# Sheet1.net
KiCad netlist of a schematic drawn in Altium Designer
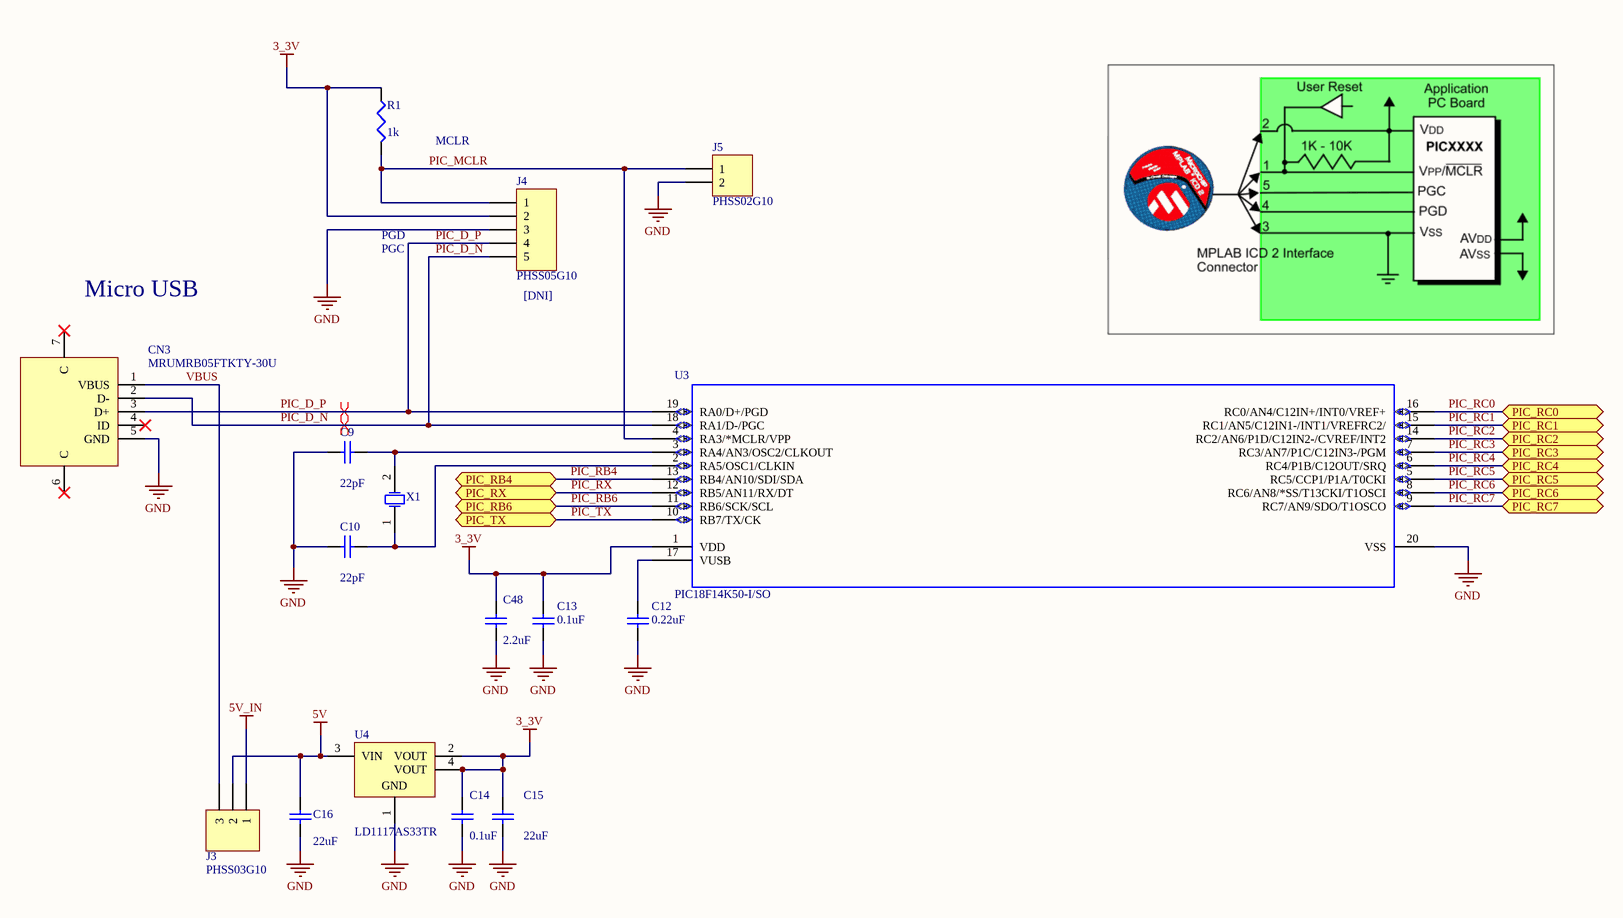
[diagram p0: Sheet1.SchDoc]

(export (version "E")
  (design (tool "Eeschema 10.0.6"))
  (components
    (comp (ref "C9")
      (value "22pF")
      (footprint "PcbLib:CHIP1608")
      (description "Capacitor (Semiconductor SIM Model)")
      (fields (field (name "Comment") "06035A220JAT2A") (field (name "PUBLISHER") "Altium Limited"))
      (libsource (lib "Miscellaneous Devices") (part "Cap Semi"))
    )
    (comp (ref "C10")
      (value "22pF")
      (footprint "PcbLib:CHIP1608")
      (description "Capacitor (Semiconductor SIM Model)")
      (fields (field (name "Comment") "06035A220JAT2A") (field (name "PUBLISHER") "Altium Limited"))
      (libsource (lib "Miscellaneous Devices") (part "Cap Semi"))
    )
    (comp (ref "C12")
      (value "0.22uF")
      (footprint "PcbLib:CHIP1608")
      (description "Capacitor (Semiconductor SIM Model)")
      (fields (field (name "Comment") "CC0603ZRY5V7BB224") (field (name "PUBLISHER") "Altium Limited"))
      (libsource (lib "Miscellaneous Devices") (part "Cap Semi"))
    )
    (comp (ref "C13")
      (value "0.1uF")
      (footprint "PcbLib:CHIP1608")
      (description "Capacitor (Semiconductor SIM Model)")
      (fields (field (name "Comment") "MC0603B104M160CT") (field (name "PUBLISHER") "Altium Limited"))
      (libsource (lib "Miscellaneous Devices") (part "Cap Semi"))
    )
    (comp (ref "C14")
      (value "0.1uF")
      (footprint "PcbLib:CHIP1608")
      (description "Capacitor (Semiconductor SIM Model)")
      (fields (field (name "Comment") "MC0603B104M160CT") (field (name "PUBLISHER") "Altium Limited"))
      (libsource (lib "Miscellaneous Devices") (part "Cap Semi"))
    )
    (comp (ref "C15")
      (value "22uF")
      (footprint "PcbLib:CHIP3216")
      (description "Capacitor (Semiconductor SIM Model)")
      (fields (field (name "Comment") "MC1206F226Z100CT") (field (name "PUBLISHER") "Altium Limited"))
      (libsource (lib "Miscellaneous Devices") (part "Cap Semi"))
    )
    (comp (ref "C16")
      (value "22uF")
      (footprint "PcbLib:CHIP3216")
      (description "Capacitor (Semiconductor SIM Model)")
      (fields (field (name "Comment") "MC1206F226Z100CT") (field (name "PUBLISHER") "Altium Limited"))
      (libsource (lib "Miscellaneous Devices") (part "Cap Semi"))
    )
    (comp (ref "C48")
      (value "2.2uF")
      (footprint "PcbLib:CHIP1608")
      (description "Capacitor (Semiconductor SIM Model)")
      (fields (field (name "Comment") "MC0603B225K6R3CT") (field (name "PUBLISHER") "Altium Limited"))
      (libsource (lib "Miscellaneous Devices") (part "Cap Semi"))
    )
    (comp (ref "CN3")
      (value "MRUMRB05FTKTY-30U")
      (footprint "MRUMRB05FTKTY-30U")
      (description "MicroUSBTypeB")
      (libsource (lib "Schlib") (part "MicroUSBTypeB"))
    )
    (comp (ref "J3")
      (value "PHSS03G10")
      (footprint "PcbLib:HDR1X3")
      (description "Header, 3-Pin")
      (fields (field (name "PUBLISHER") "Altium Limited"))
      (libsource (lib "Miscellaneous Connectors") (part "Header 3"))
    )
    (comp (ref "J4")
      (value "PHSS05G10")
      (footprint "PcbLib:HDR1X5")
      (description "Header, 5-Pin")
      (fields (field (name "ASSEMBLY") "[DNI]") (field (name "PUBLISHER") "Altium Limited"))
      (libsource (lib "Miscellaneous Connectors") (part "Header 5"))
    )
    (comp (ref "J5")
      (value "PHSS02G10")
      (footprint "PcbLib:HDR1X2")
      (description "Header, 2-Pin")
      (fields (field (name "PUBLISHER") "Altium Limited"))
      (libsource (lib "Miscellaneous Connectors") (part "Header 2"))
    )
    (comp (ref "R1")
      (value "1k")
      (footprint "PcbLib:CHIP1608")
      (description "Resistor")
      (fields (field (name "Comment") "MCMR06X1001FTL") (field (name "PUBLISHER") "Altium Limited"))
      (libsource (lib "Miscellaneous Devices") (part "Res3"))
    )
    (comp (ref "U3")
      (value "PIC18F14K50-I/SO")
      (footprint "PcbLib:PIC18F14K50-SO")
      (description "MICROCHIPS")
      (libsource (lib "Schlib1") (part "PIC18F14K50"))
    )
    (comp (ref "U4")
      (value "LD1117AS33TR")
      (footprint "SOT-223_N")
      (description "1A, Low Drop Positive Voltage Regulator, 3.3V, 4-Pin SOT-223, Tape and Reel")
      (libsource (lib "STMicroelectronics Power Management Linear Regulator") (part "LD1117AS33TR"))
    )
    (comp (ref "X1")
      (value "SMD49S-12M1630F")
      (footprint "ABLS-25.000MHZ-B2F-T")
      (description "MEC")
      (libsource (lib "Schlib1") (part "ABLS-25.000MHZ-B2F-T"))
    )
  )
  (nets
    (net (code "1") (name "/PIC_D_N") (class "Default")
      (node (ref "CN3") (pin "2") (pinfunction "D-_2") (pintype "passive"))
      (node (ref "J4") (pin "5") (pinfunction "5_5") (pintype "passive"))
      (node (ref "U3") (pin "18") (pinfunction "RA1/D-/PGC_18") (pintype "bidirectional"))
    )
    (net (code "2") (name "/PIC_D_P") (class "Default")
      (node (ref "CN3") (pin "3") (pinfunction "D+_3") (pintype "passive"))
      (node (ref "J4") (pin "4") (pinfunction "4_4") (pintype "passive"))
      (node (ref "U3") (pin "19") (pinfunction "RA0/D+/PGD_19") (pintype "bidirectional"))
    )
    (net (code "3") (name "/PIC_MCLR") (class "Default")
      (node (ref "J4") (pin "1") (pinfunction "1_1") (pintype "passive"))
      (node (ref "J5") (pin "1") (pinfunction "1_1") (pintype "passive"))
      (node (ref "R1") (pin "2") (pinfunction "2_2") (pintype "passive"))
      (node (ref "U3") (pin "4") (pinfunction "RA3/*MCLR/VPP_4") (pintype "bidirectional"))
    )
    (net (code "4") (name "/PIC_RB4") (class "Default")
      (node (ref "U3") (pin "13") (pinfunction "RB4/AN10/SDI/SDA_13") (pintype "bidirectional"))
    )
    (net (code "5") (name "/PIC_RB6") (class "Default")
      (node (ref "U3") (pin "11") (pinfunction "RB6/SCK/SCL_11") (pintype "bidirectional"))
    )
    (net (code "6") (name "/PIC_RC0") (class "Default")
      (node (ref "U3") (pin "16") (pinfunction "RC0/AN4/C12IN+/INT0/VREF+_16") (pintype "bidirectional"))
    )
    (net (code "7") (name "/PIC_RC1") (class "Default")
      (node (ref "U3") (pin "15") (pinfunction "RC1/AN5/C12IN1-/INT1/VREFRC2/_15") (pintype "bidirectional"))
    )
    (net (code "8") (name "/PIC_RC2") (class "Default")
      (node (ref "U3") (pin "14") (pinfunction "RC2/AN6/P1D/C12IN2-/CVREF/INT2_14") (pintype "bidirectional"))
    )
    (net (code "9") (name "/PIC_RC3") (class "Default")
      (node (ref "U3") (pin "7") (pinfunction "RC3/AN7/P1C/C12IN3-/PGM_7") (pintype "bidirectional"))
    )
    (net (code "10") (name "/PIC_RC4") (class "Default")
      (node (ref "U3") (pin "6") (pinfunction "RC4/P1B/C12OUT/SRQ_6") (pintype "bidirectional"))
    )
    (net (code "11") (name "/PIC_RC5") (class "Default")
      (node (ref "U3") (pin "5") (pinfunction "RC5/CCP1/P1A/T0CKI_5") (pintype "bidirectional"))
    )
    (net (code "12") (name "/PIC_RC6") (class "Default")
      (node (ref "U3") (pin "8") (pinfunction "RC6/AN8/*SS/T13CKI/T1OSCI_8") (pintype "bidirectional"))
    )
    (net (code "13") (name "/PIC_RC7") (class "Default")
      (node (ref "U3") (pin "9") (pinfunction "RC7/AN9/SDO/T1OSCO_9") (pintype "bidirectional"))
    )
    (net (code "14") (name "/PIC_RX") (class "Default")
      (node (ref "U3") (pin "12") (pinfunction "RB5/AN11/RX/DT_12") (pintype "bidirectional"))
    )
    (net (code "15") (name "/PIC_TX") (class "Default")
      (node (ref "U3") (pin "10") (pinfunction "RB7/TX/CK_10") (pintype "bidirectional"))
    )
    (net (code "16") (name "/VBUS") (class "Default")
      (node (ref "CN3") (pin "1") (pinfunction "VBUS_1") (pintype "passive"))
      (node (ref "J3") (pin "3") (pinfunction "3_3") (pintype "passive"))
    )
    (net (code "17") (name "3_3V") (class "Default")
      (node (ref "C13") (pin "2") (pinfunction "2_2") (pintype "passive"))
      (node (ref "C14") (pin "2") (pinfunction "2_2") (pintype "passive"))
      (node (ref "C15") (pin "2") (pinfunction "2_2") (pintype "passive"))
      (node (ref "C48") (pin "2") (pinfunction "2_2") (pintype "passive"))
      (node (ref "J4") (pin "2") (pinfunction "2_2") (pintype "passive"))
      (node (ref "R1") (pin "1") (pinfunction "1_1") (pintype "passive"))
      (node (ref "U3") (pin "1") (pinfunction "VDD_1") (pintype "power_in"))
      (node (ref "U4") (pin "2") (pinfunction "VOUT_2") (pintype "power_in"))
      (node (ref "U4") (pin "4") (pinfunction "VOUT_4") (pintype "power_in"))
    )
    (net (code "18") (name "5V") (class "Default")
      (node (ref "C16") (pin "2") (pinfunction "2_2") (pintype "passive"))
      (node (ref "J3") (pin "2") (pinfunction "2_2") (pintype "passive"))
      (node (ref "U4") (pin "3") (pinfunction "VIN_3") (pintype "power_in"))
    )
    (net (code "19") (name "5V_IN") (class "Default")
      (node (ref "J3") (pin "1") (pinfunction "1_1") (pintype "passive"))
    )
    (net (code "20") (name "GND") (class "Default")
      (node (ref "C10") (pin "1") (pinfunction "1_1") (pintype "passive"))
      (node (ref "C12") (pin "1") (pinfunction "1_1") (pintype "passive"))
      (node (ref "C13") (pin "1") (pinfunction "1_1") (pintype "passive"))
      (node (ref "C14") (pin "1") (pinfunction "1_1") (pintype "passive"))
      (node (ref "C15") (pin "1") (pinfunction "1_1") (pintype "passive"))
      (node (ref "C16") (pin "1") (pinfunction "1_1") (pintype "passive"))
      (node (ref "C48") (pin "1") (pinfunction "1_1") (pintype "passive"))
      (node (ref "C9") (pin "1") (pinfunction "1_1") (pintype "passive"))
      (node (ref "CN3") (pin "5") (pinfunction "GND_5") (pintype "passive"))
      (node (ref "J4") (pin "3") (pinfunction "3_3") (pintype "passive"))
      (node (ref "J5") (pin "2") (pinfunction "2_2") (pintype "passive"))
      (node (ref "U3") (pin "20") (pinfunction "VSS_20") (pintype "power_in"))
      (node (ref "U4") (pin "1") (pinfunction "GND_1") (pintype "power_in"))
    )
    (net (code "21") (name "Net-(U3-RA4{slash}AN3{slash}OSC2{slash}CLKOUT)") (class "Default")
      (node (ref "C9") (pin "2") (pinfunction "2_2") (pintype "passive"))
      (node (ref "U3") (pin "3") (pinfunction "RA4/AN3/OSC2/CLKOUT_3") (pintype "bidirectional"))
      (node (ref "X1") (pin "2") (pinfunction "OSC2_2") (pintype "passive"))
    )
    (net (code "22") (name "Net-(U3-RA5{slash}OSC1{slash}CLKIN)") (class "Default")
      (node (ref "C10") (pin "2") (pinfunction "2_2") (pintype "passive"))
      (node (ref "U3") (pin "2") (pinfunction "RA5/OSC1/CLKIN_2") (pintype "bidirectional"))
      (node (ref "X1") (pin "1") (pinfunction "OSC1_1") (pintype "passive"))
    )
    (net (code "23") (name "Net-(U3-VUSB)") (class "Default")
      (node (ref "C12") (pin "2") (pinfunction "2_2") (pintype "passive"))
      (node (ref "U3") (pin "17") (pinfunction "VUSB_17") (pintype "power_in"))
    )
    (net (code "24") (name "unconnected-(CN3-C-Pad6)") (class "Default")
      (node (ref "CN3") (pin "6") (pinfunction "C_6") (pintype "passive+no_connect"))
    )
    (net (code "25") (name "unconnected-(CN3-C-Pad7)") (class "Default")
      (node (ref "CN3") (pin "7") (pinfunction "C_7") (pintype "passive+no_connect"))
    )
    (net (code "26") (name "unconnected-(CN3-ID-Pad4)") (class "Default")
      (node (ref "CN3") (pin "4") (pinfunction "ID_4") (pintype "passive+no_connect"))
    )
  )
)
